# SCH_nfc_card.net
KiCad netlist of a schematic drawn in EasyEDA
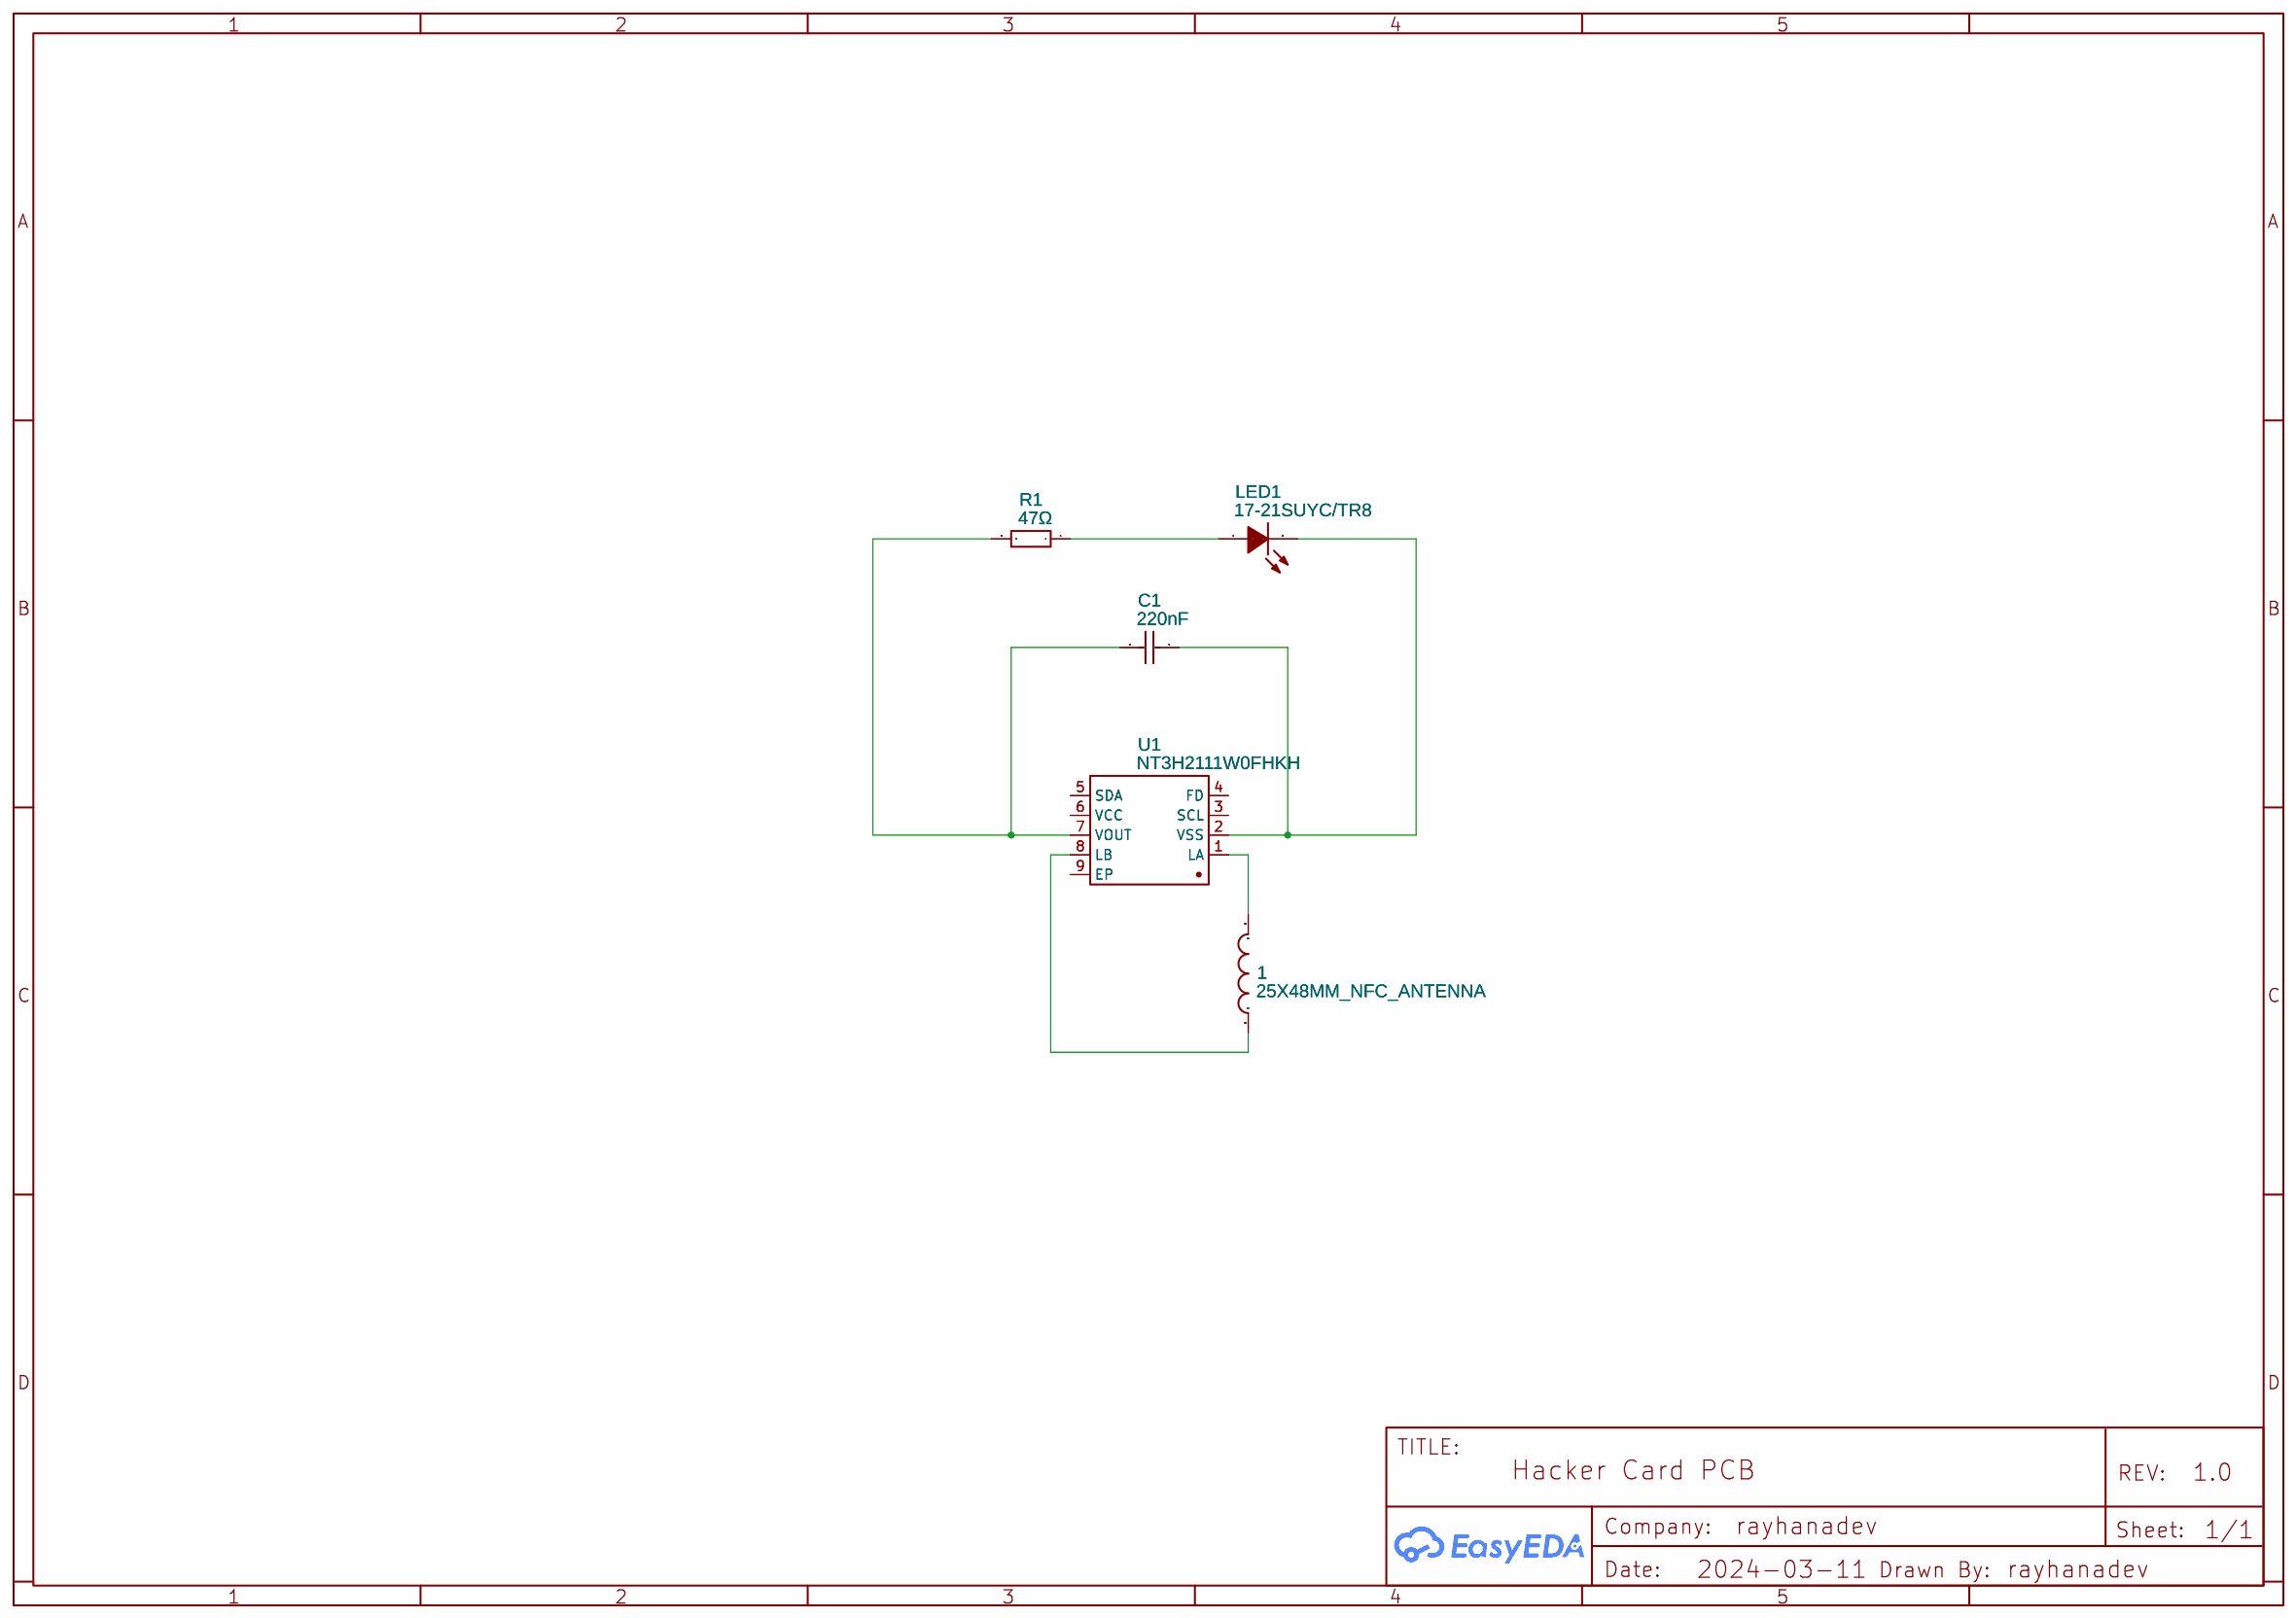
[diagram p0: schematic sheet]

(export (version "E")
  (design (tool "Eeschema 10.0.6"))
  (components
    (comp (ref "1") (value "25X48MM_NFC_ANTENNA") (libsource (lib "") (part "25X48MM_NFC_ANTENNA")))
    (comp (ref "C1")
      (value "220nF")
      (fields
        (field (name "Manufacturer Part") "CL10B224KA8NNNC")
        (field (name "Manufacturer") "SAMSUNG(三星)")
      )
      (libsource (lib "") (part "CL10B224KA8NNNC"))
    )
    (comp (ref "LED1")
      (value "17-21SUYC/TR8")
      (fields (field (name "Manufacturer Part") "KT-0805黄灯") (field (name "Manufacturer") "KENTO"))
      (libsource (lib "") (part "17-21SUYC/TR8"))
    )
    (comp (ref "R1")
      (value "47Ω")
      (fields
        (field (name "Manufacturer Part") "0603WAF470JT5E")
        (field (name "Manufacturer") "UNI-ROYAL(厚声)")
      )
      (libsource (lib "") (part "0603WAF470JT5E"))
    )
    (comp (ref "U1")
      (value "NT3H2111W0FHKH")
      (fields (field (name "Manufacturer") "NXP(恩智浦)"))
      (libsource (lib "") (part "NT3H2111W0FHKH"))
    )
  )
  (nets
    (net (code "1") (name "Net-(LED1-+)") (class "Default")
      (node (ref "LED1") (pin "1") (pinfunction "+_1") (pintype "unspecified"))
      (node (ref "R1") (pin "1") (pinfunction "1_1") (pintype "input"))
    )
    (net (code "2") (name "Net-(LED1--)") (class "Default")
      (node (ref "C1") (pin "1") (pinfunction "1_1") (pintype "input"))
      (node (ref "LED1") (pin "2") (pinfunction "-_2") (pintype "unspecified"))
      (node (ref "U1") (pin "2") (pinfunction "VSS_2") (pintype "unspecified"))
    )
    (net (code "3") (name "Net-(U1-LA)") (class "Default")
      (node (ref "1") (pin "P$2") (pinfunction "P$2_P$2") (pintype "bidirectional"))
      (node (ref "U1") (pin "1") (pinfunction "LA_1") (pintype "unspecified"))
    )
    (net (code "4") (name "Net-(U1-LB)") (class "Default")
      (node (ref "1") (pin "P$1") (pinfunction "P$1_P$1") (pintype "bidirectional"))
      (node (ref "U1") (pin "8") (pinfunction "LB_8") (pintype "unspecified"))
    )
    (net (code "5") (name "Net-(U1-VOUT)") (class "Default")
      (node (ref "C1") (pin "2") (pinfunction "2_2") (pintype "input"))
      (node (ref "R1") (pin "2") (pinfunction "2_2") (pintype "input"))
      (node (ref "U1") (pin "7") (pinfunction "VOUT_7") (pintype "unspecified"))
    )
    (net (code "6") (name "unconnected-(U1-EP-Pad9)") (class "Default")
      (node (ref "U1") (pin "9") (pinfunction "EP_9") (pintype "unspecified"))
    )
    (net (code "7") (name "unconnected-(U1-FD-Pad4)") (class "Default")
      (node (ref "U1") (pin "4") (pinfunction "FD_4") (pintype "unspecified"))
    )
    (net (code "8") (name "unconnected-(U1-SCL-Pad3)") (class "Default")
      (node (ref "U1") (pin "3") (pinfunction "SCL_3") (pintype "unspecified"))
    )
    (net (code "9") (name "unconnected-(U1-SDA-Pad5)") (class "Default")
      (node (ref "U1") (pin "5") (pinfunction "SDA_5") (pintype "unspecified"))
    )
    (net (code "10") (name "unconnected-(U1-VCC-Pad6)") (class "Default")
      (node (ref "U1") (pin "6") (pinfunction "VCC_6") (pintype "unspecified"))
    )
  )
)
